# Zocalo-mcp2551-SOIC.net
KiCad netlist of a schematic drawn in EAGLE
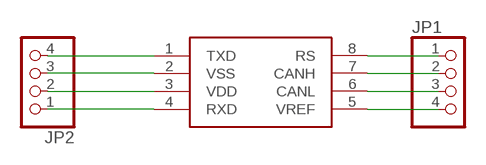
[diagram p0: schematic, sheet 1]

(export (version "E")
  (design (tool "Eeschema 10.0.6"))
  (components
    (comp (ref "JP1")
      (value "PINHD-1X4")
      (footprint "eagle-import:1X04")
      (libsource (lib "eagle-import") (part "PINHD-1X4"))
    )
    (comp (ref "JP2")
      (value "PINHD-1X4")
      (footprint "eagle-import:1X04")
      (libsource (lib "eagle-import") (part "PINHD-1X4"))
    )
    (comp (ref "U1")
      (value "MCP2551")
      (footprint "eagle-import:SO08")
      (libsource (lib "eagle-import") (part "MCP2551"))
    )
  )
  (nets
    (net (code "1") (name "Net-(U1-CANH)") (class "Default")
      (node (ref "JP1") (pin "2") (pinfunction "2_2") (pintype "passive"))
      (node (ref "U1") (pin "7") (pinfunction "CANH_7") (pintype "bidirectional"))
    )
    (net (code "2") (name "Net-(U1-CANL)") (class "Default")
      (node (ref "JP1") (pin "3") (pinfunction "3_3") (pintype "passive"))
      (node (ref "U1") (pin "6") (pinfunction "CANL_6") (pintype "bidirectional"))
    )
    (net (code "3") (name "Net-(U1-RS)") (class "Default")
      (node (ref "JP1") (pin "1") (pinfunction "1_1") (pintype "passive"))
      (node (ref "U1") (pin "8") (pinfunction "RS_8") (pintype "bidirectional"))
    )
    (net (code "4") (name "Net-(U1-RXD)") (class "Default")
      (node (ref "JP2") (pin "1") (pinfunction "1_1") (pintype "passive"))
      (node (ref "U1") (pin "4") (pinfunction "RXD_4") (pintype "bidirectional"))
    )
    (net (code "5") (name "Net-(U1-TXD)") (class "Default")
      (node (ref "JP2") (pin "4") (pinfunction "4_4") (pintype "passive"))
      (node (ref "U1") (pin "1") (pinfunction "TXD_1") (pintype "bidirectional"))
    )
    (net (code "6") (name "Net-(U1-VDD)") (class "Default")
      (node (ref "JP2") (pin "2") (pinfunction "2_2") (pintype "passive"))
      (node (ref "U1") (pin "3") (pinfunction "VDD_3") (pintype "bidirectional"))
    )
    (net (code "7") (name "Net-(U1-VREF)") (class "Default")
      (node (ref "JP1") (pin "4") (pinfunction "4_4") (pintype "passive"))
      (node (ref "U1") (pin "5") (pinfunction "VREF_5") (pintype "bidirectional"))
    )
    (net (code "8") (name "Net-(U1-VSS)") (class "Default")
      (node (ref "JP2") (pin "3") (pinfunction "3_3") (pintype "passive"))
      (node (ref "U1") (pin "2") (pinfunction "VSS_2") (pintype "bidirectional"))
    )
  )
)
